# SX1276.net
KiCad netlist of a schematic drawn in Altium Designer
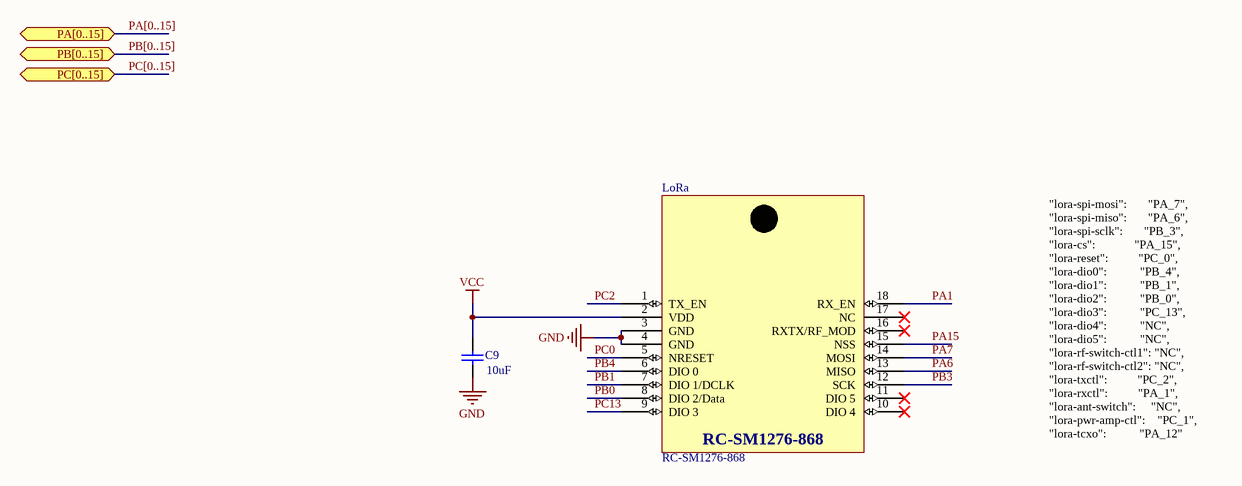
[diagram p0: SX1276.SchDoc]

(export (version "E")
  (design (tool "Eeschema 10.0.6"))
  (components
    (comp (ref "C9")
      (value "10uF")
      (footprint "CAPC2013X145X20ML20")
      (fields
        (field (name "MANUFACTURER") "TDK")
        (field (name "TOLERANCE") "±10%")
        (field (name "PCN PART NUMBER") "MLCCPartNumberChange30/Nov/2012")
      )
      (libsource (lib "Altium Content Vault") (part "CAP-NP-2"))
    )
    (comp (ref "LoRa")
      (value "RC-SM1276-868")
      (footprint "RC-SM1276-868")
      (description "https://www.radiocontrolli.com/it/componente/97/rc-sm1276-868")
      (libsource (lib " Faculty of Electrical Engineering and Computing") (part "RC-SM1276-868"))
    )
  )
  (nets
    (net (code "38") (name "/PA1") (class "Default")
      (node (ref "LoRa") (pin "18") (pinfunction "RX_EN_18") (pintype "bidirectional"))
    )
    (net (code "39") (name "/PA6") (class "Default")
      (node (ref "LoRa") (pin "13") (pinfunction "MISO_13") (pintype "bidirectional"))
    )
    (net (code "40") (name "/PA7") (class "Default")
      (node (ref "LoRa") (pin "14") (pinfunction "MOSI_14") (pintype "bidirectional"))
    )
    (net (code "41") (name "/PA15") (class "Default")
      (node (ref "LoRa") (pin "15") (pinfunction "NSS_15") (pintype "bidirectional"))
    )
    (net (code "43") (name "/PB0") (class "Default")
      (node (ref "LoRa") (pin "8") (pinfunction "DIO_2/Data_8") (pintype "bidirectional"))
    )
    (net (code "44") (name "/PB1") (class "Default")
      (node (ref "LoRa") (pin "7") (pinfunction "DIO_1/DCLK_7") (pintype "bidirectional"))
    )
    (net (code "45") (name "/PB3") (class "Default")
      (node (ref "LoRa") (pin "12") (pinfunction "SCK_12") (pintype "bidirectional"))
    )
    (net (code "46") (name "/PB4") (class "Default")
      (node (ref "LoRa") (pin "6") (pinfunction "DIO_0_6") (pintype "bidirectional"))
    )
    (net (code "48") (name "/PC0") (class "Default")
      (node (ref "LoRa") (pin "5") (pinfunction "NRESET_5") (pintype "bidirectional"))
    )
    (net (code "49") (name "/PC2") (class "Default")
      (node (ref "LoRa") (pin "1") (pinfunction "TX_EN_1") (pintype "bidirectional"))
    )
    (net (code "50") (name "/PC13") (class "Default")
      (node (ref "LoRa") (pin "9") (pinfunction "DIO_3_9") (pintype "bidirectional"))
    )
    (net (code "52") (name "GND") (class "Default")
      (node (ref "C9") (pin "1") (pinfunction "1_1") (pintype "passive"))
      (node (ref "LoRa") (pin "3") (pinfunction "GND_3") (pintype "power_in"))
      (node (ref "LoRa") (pin "4") (pinfunction "GND_4") (pintype "power_in"))
    )
    (net (code "53") (name "VCC") (class "Default")
      (node (ref "C9") (pin "2") (pinfunction "2_2") (pintype "passive"))
      (node (ref "LoRa") (pin "2") (pinfunction "VDD_2") (pintype "power_in"))
    )
    (net (code "54") (name "unconnected-(LoRa-DIO_4-Pad10)") (class "Default")
      (node (ref "LoRa") (pin "10") (pinfunction "DIO_4_10") (pintype "bidirectional+no_connect"))
    )
    (net (code "55") (name "unconnected-(LoRa-DIO_5-Pad11)") (class "Default")
      (node (ref "LoRa") (pin "11") (pinfunction "DIO_5_11") (pintype "bidirectional+no_connect"))
    )
    (net (code "56") (name "unconnected-(LoRa-NC-Pad17)") (class "Default")
      (node (ref "LoRa") (pin "17") (pinfunction "NC_17") (pintype "tri_state+no_connect"))
    )
    (net (code "57") (name "unconnected-(LoRa-RXTX{slash}RF_MOD-Pad16)") (class "Default")
      (node (ref "LoRa") (pin "16") (pinfunction "RXTX/RF_MOD_16") (pintype "bidirectional+no_connect"))
    )
  )
)
